# PROC054D_System_3V3_Supply.net
KiCad netlist of a schematic drawn in Altium Designer
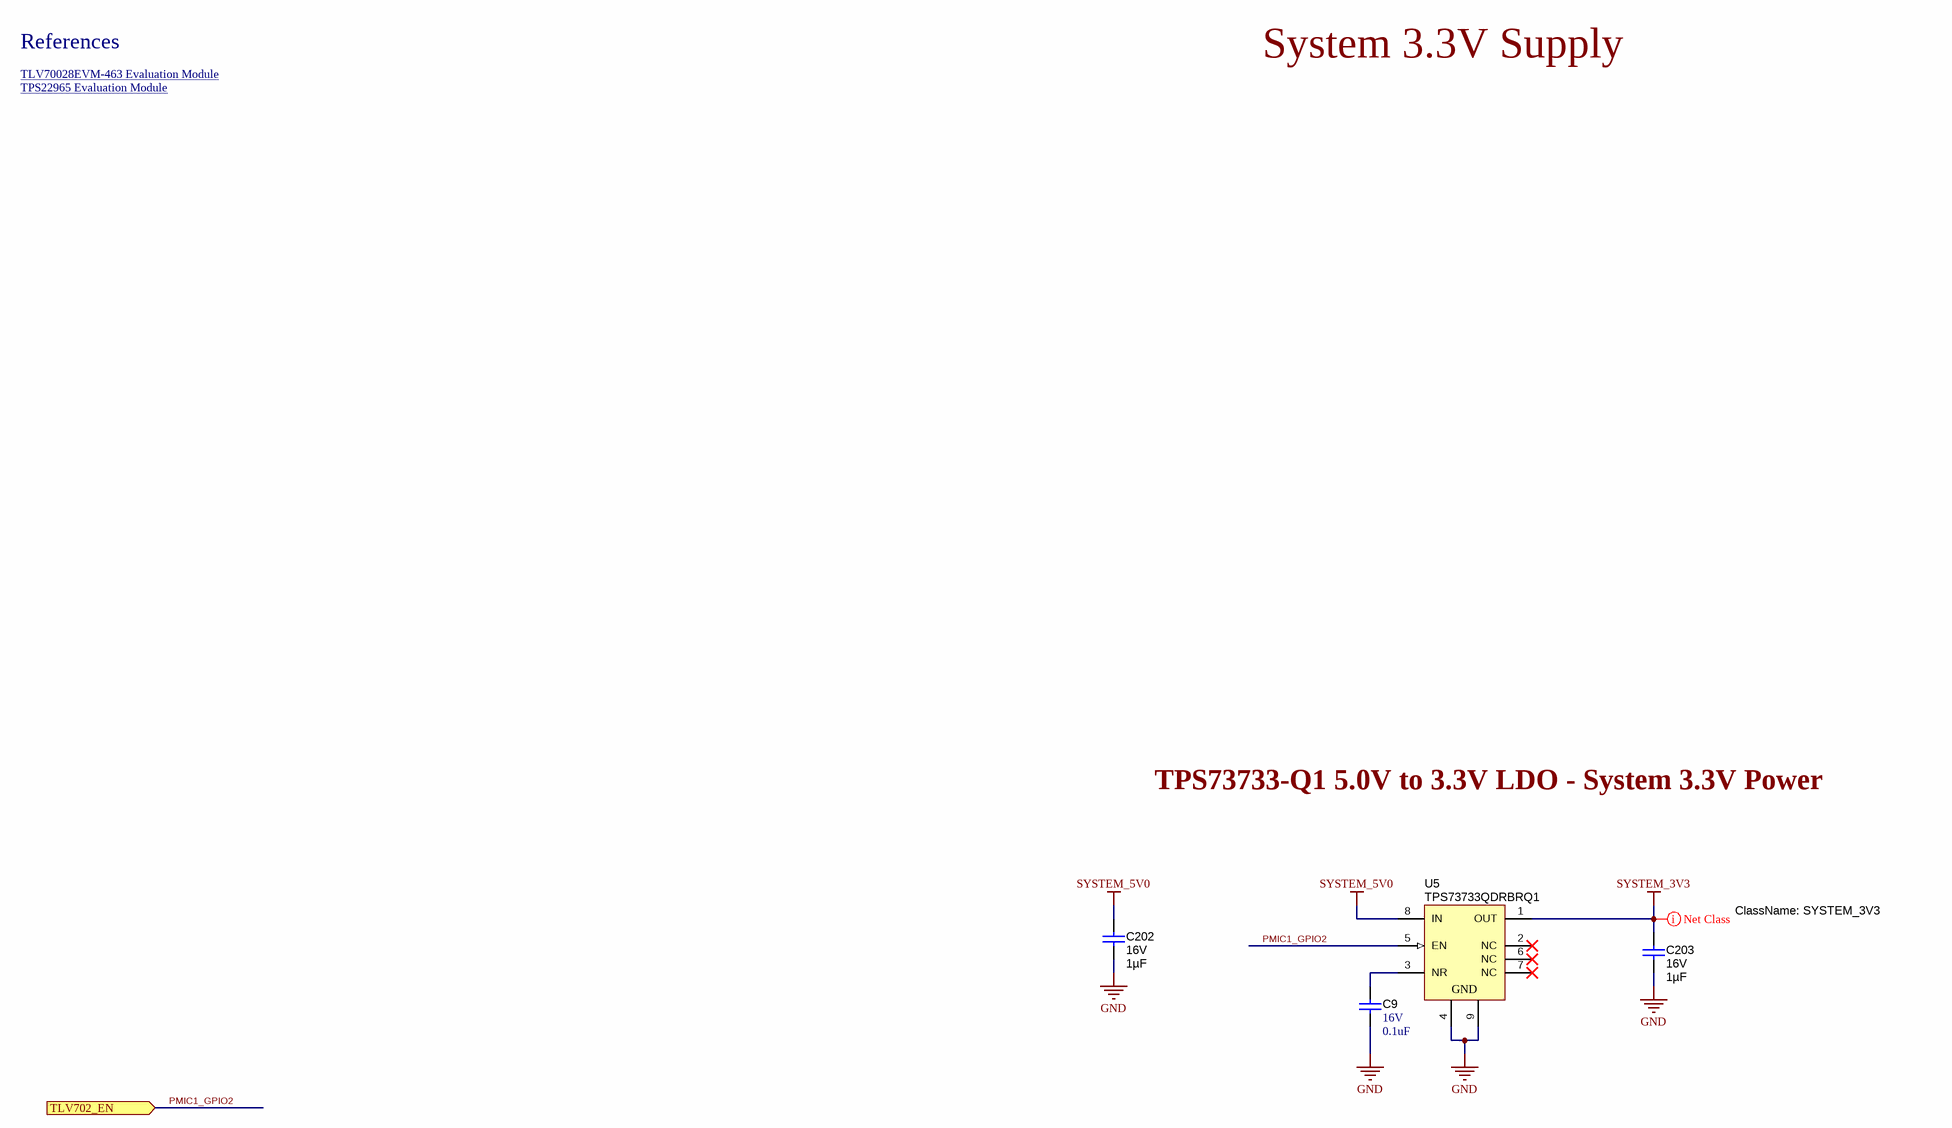
[diagram p0: PROC054D_System_3V3_Supply.SchDoc]

(export (version "E")
  (design (tool "Eeschema 10.0.6"))
  (components
    (comp (ref "C9")
      (value "GCM155R71C104KA55D")
      (footprint "0402")
      (description "CAP, CERM, 0.1 uF, 16 V, +/- 10%, X7R, 0402")
      (fields
        (field (name "MANUFACTURER") "MuRata")
        (field (name "VDC_V") "16V")
        (field (name "VALUEDISPLAYED") "0.1uF")
        (field (name "PUBLISHER") "Texas Instruments")
      )
      (libsource (lib "Altium Vault - TI") (part "Capacitor"))
    )
    (comp (ref "C202")
      (value "GCM188R71C105KA64J")
      (footprint "0603")
      (description "CAP, CERM, 1 µF, 16 V,+/- 10%, X7R, AEC-Q200 Grade 1, 0603")
      (fields
        (field (name "MANUFACTURER") "MuRata")
        (field (name "VDC_V") "16V")
        (field (name "VALUEDISPLAYED") "1µF")
      )
      (libsource (lib "Altium Vault - TI") (part "Capacitor"))
    )
    (comp (ref "C203")
      (value "GCM188R71C105KA64J")
      (footprint "0603")
      (description "CAP, CERM, 1 µF, 16 V,+/- 10%, X7R, AEC-Q200 Grade 1, 0603")
      (fields
        (field (name "MANUFACTURER") "MuRata")
        (field (name "VDC_V") "16V")
        (field (name "VALUEDISPLAYED") "1µF")
      )
      (libsource (lib "Altium Vault - TI") (part "Capacitor"))
    )
    (comp (ref "U5")
      (value "TPS73733QDRBRQ1")
      (footprint "DRB0008A")
      (fields (field (name "MANUFACTURER") "Texas Instruments") (field (name "PARTNUMBER") "TPS73733QDRBRQ1"))
      (libsource (lib "Altium Vault - TI") (part "TI-TPS73733-Q1DRB8-1750X1500TP"))
    )
  )
  (nets
    (net (code "1") (name "/PMIC1_GPIO2") (class "Default")
      (node (ref "U5") (pin "5") (pinfunction "EN_5") (pintype "input"))
    )
    (net (code "2") (name "GND") (class "Default")
      (node (ref "C202") (pin "2") (pinfunction "2_2") (pintype "passive"))
      (node (ref "C203") (pin "2") (pinfunction "2_2") (pintype "passive"))
      (node (ref "C9") (pin "2") (pinfunction "2_2") (pintype "passive"))
      (node (ref "U5") (pin "4") (pinfunction "GND_4") (pintype "power_in"))
      (node (ref "U5") (pin "9") (pinfunction "GND_9") (pintype "power_in"))
    )
    (net (code "3") (name "Net-(U5-NR)") (class "Default")
      (node (ref "C9") (pin "1") (pinfunction "1_1") (pintype "passive"))
      (node (ref "U5") (pin "3") (pinfunction "NR_3") (pintype "passive"))
    )
    (net (code "4") (name "SYSTEM_3V3") (class "Default")
      (node (ref "C203") (pin "1") (pinfunction "1_1") (pintype "passive"))
      (node (ref "U5") (pin "1") (pinfunction "OUT_1") (pintype "power_in"))
    )
    (net (code "5") (name "SYSTEM_5V0") (class "Default")
      (node (ref "C202") (pin "1") (pinfunction "1_1") (pintype "passive"))
      (node (ref "U5") (pin "8") (pinfunction "IN_8") (pintype "power_in"))
    )
    (net (code "6") (name "unconnected-(U5-NC-Pad2)") (class "Default")
      (node (ref "U5") (pin "2") (pinfunction "NC_2") (pintype "passive+no_connect"))
    )
    (net (code "7") (name "unconnected-(U5-NC-Pad6)") (class "Default")
      (node (ref "U5") (pin "6") (pinfunction "NC_6") (pintype "passive+no_connect"))
    )
    (net (code "8") (name "unconnected-(U5-NC-Pad7)") (class "Default")
      (node (ref "U5") (pin "7") (pinfunction "NC_7") (pintype "passive+no_connect"))
    )
  )
)
